# ArdulonShiled_for_Arduino_DUE.net
KiCad netlist of a schematic drawn in EAGLE
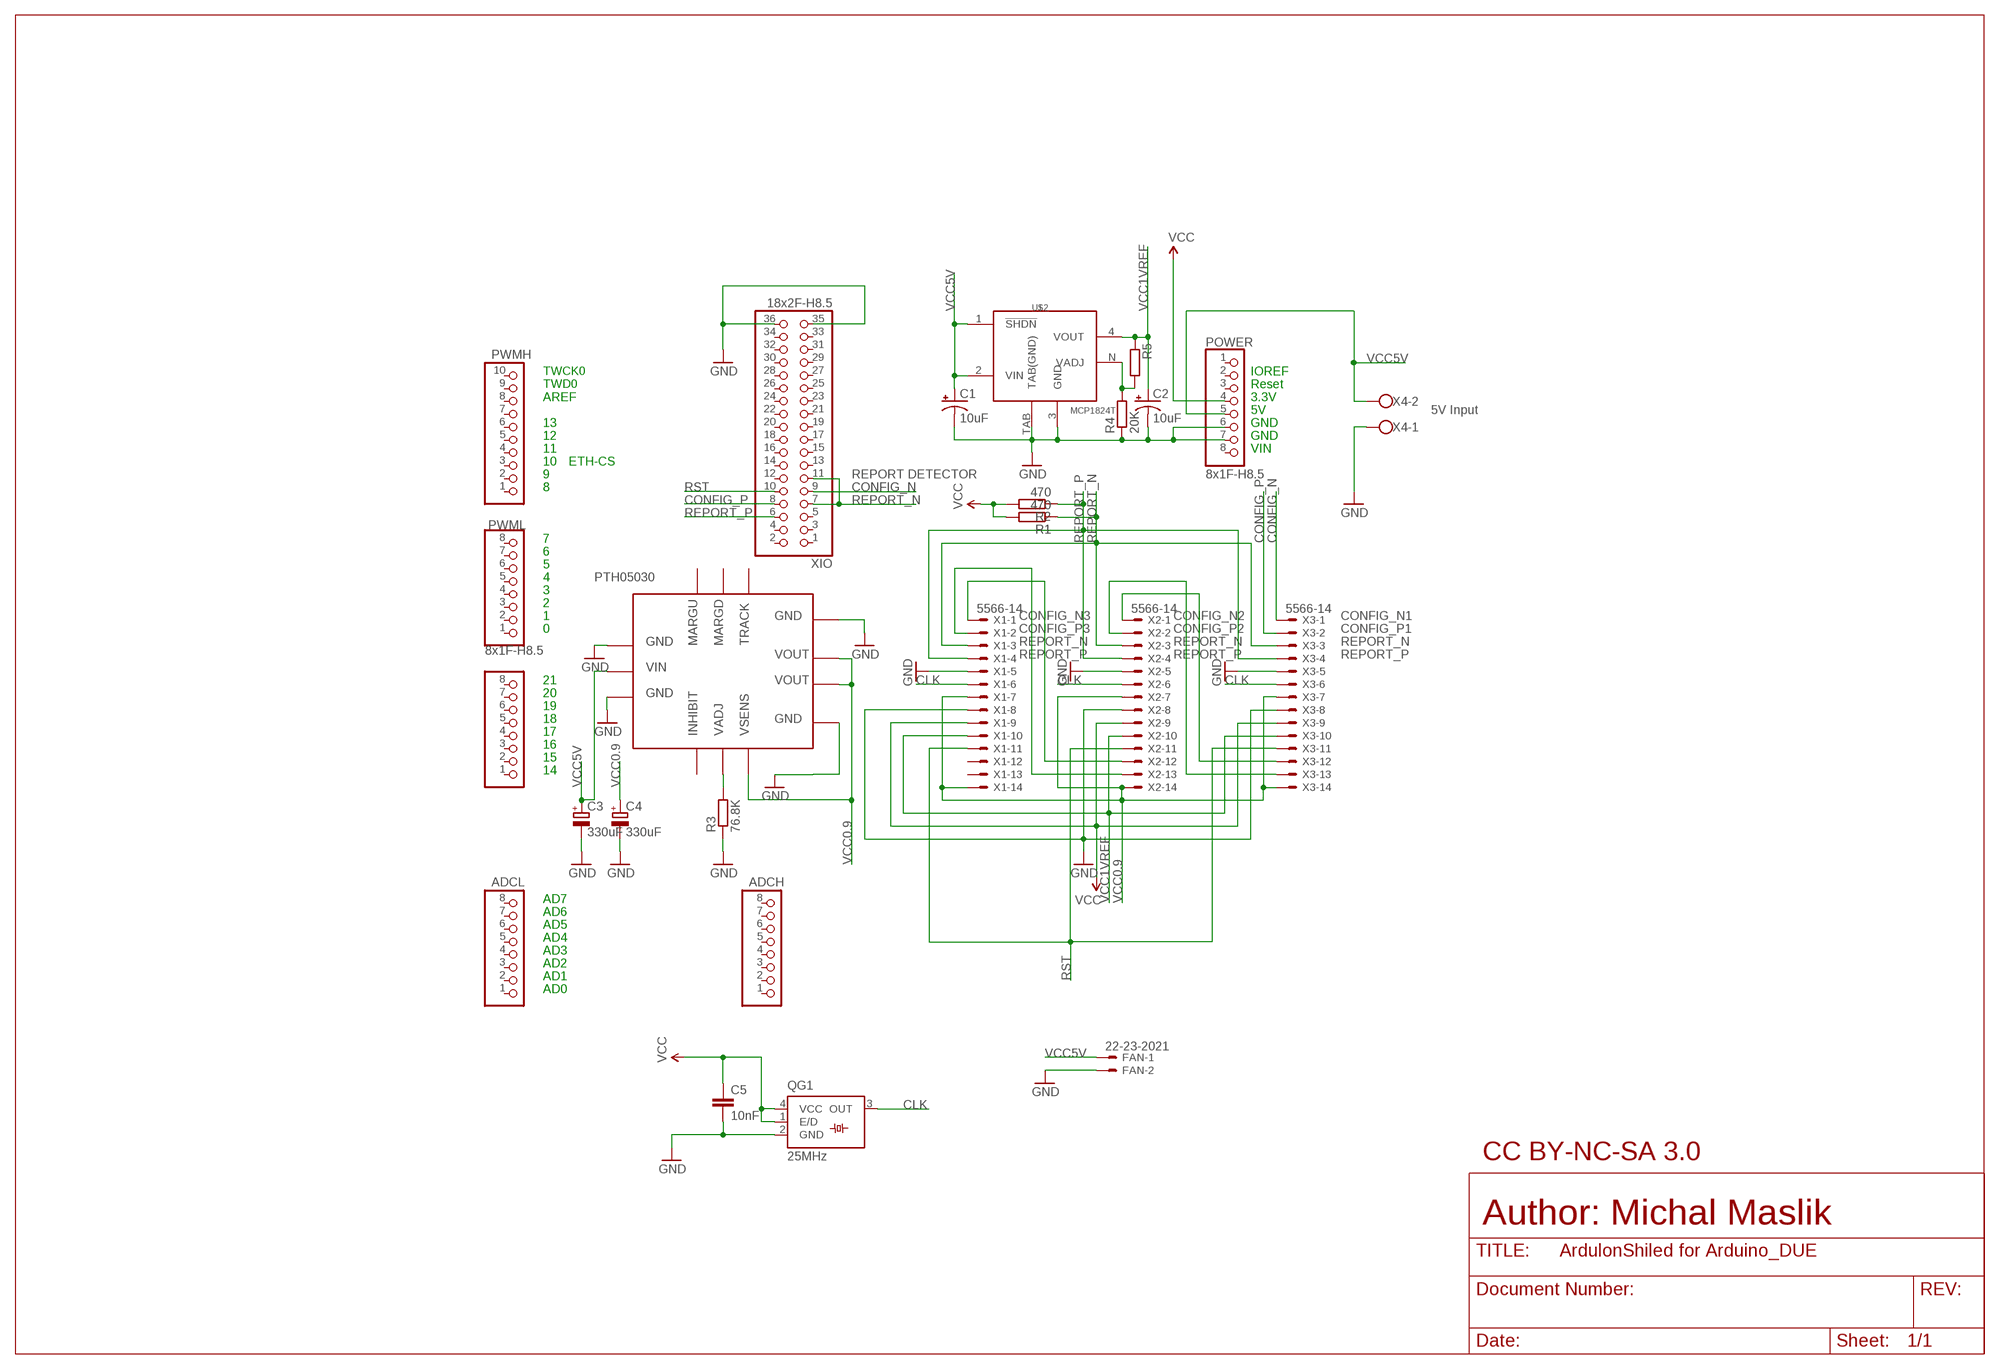
[diagram p0: schematic, sheet 1]

(export (version "E")
  (design (tool "Eeschema 10.0.6"))
  (components
    (comp (ref "ADCH")
      (value "8x1F-H8.5")
      (footprint "eagle-import:1X08")
      (libsource (lib "eagle-import") (part "PINHD-1X8"))
    )
    (comp (ref "ADCL")
      (value "8x1F-H8.5")
      (footprint "eagle-import:1X08")
      (libsource (lib "eagle-import") (part "PINHD-1X8"))
    )
    (comp (ref "C1")
      (value "10uF")
      (footprint "eagle-import:EIA3528-KIT")
      (libsource (lib "eagle-import") (part "CAP_POL3528-KIT"))
    )
    (comp (ref "C2")
      (value "10uF")
      (footprint "eagle-import:EIA3528-KIT")
      (libsource (lib "eagle-import") (part "CAP_POL3528-KIT"))
    )
    (comp (ref "C3")
      (value "330uF")
      (footprint "eagle-import:SMC_E")
      (libsource (lib "eagle-import") (part "CPOL-EUSMCE"))
    )
    (comp (ref "C4")
      (value "330uF")
      (footprint "eagle-import:SMC_E")
      (libsource (lib "eagle-import") (part "CPOL-EUSMCE"))
    )
    (comp (ref "C5")
      (value "10nF")
      (footprint "eagle-import:C0805")
      (libsource (lib "eagle-import") (part "C-EUC0805"))
    )
    (comp (ref "COMMUNICATION")
      (value "8x1F-H8.5")
      (footprint "eagle-import:1X08")
      (libsource (lib "eagle-import") (part "PINHD-1X8"))
    )
    (comp (ref "FAN")
      (value "22-23-2021")
      (footprint "eagle-import:22-23-2021")
      (libsource (lib "eagle-import") (part "22-23-2021"))
    )
    (comp (ref "POWER")
      (value "8x1F-H8.5")
      (footprint "eagle-import:1X08")
      (libsource (lib "eagle-import") (part "PINHD-1X8"))
    )
    (comp (ref "PWMH")
      (value "10x1F-H8.5")
      (footprint "eagle-import:1X10")
      (libsource (lib "eagle-import") (part "PINHD-1X10"))
    )
    (comp (ref "PWML")
      (value "8x1F-H8.5")
      (footprint "eagle-import:1X08")
      (libsource (lib "eagle-import") (part "PINHD-1X8"))
    )
    (comp (ref "QG1")
      (value "25MHz")
      (footprint "eagle-import:SM77H")
      (libsource (lib "eagle-import") (part "SM77H"))
    )
    (comp (ref "R1")
      (value "470")
      (footprint "eagle-import:M0805")
      (libsource (lib "eagle-import") (part "R-EU_M0805"))
    )
    (comp (ref "R2")
      (value "470")
      (footprint "eagle-import:M0805")
      (libsource (lib "eagle-import") (part "R-EU_M0805"))
    )
    (comp (ref "R3")
      (value "76.8K")
      (footprint "eagle-import:M0805")
      (libsource (lib "eagle-import") (part "R-EU_M0805"))
    )
    (comp (ref "R4")
      (value "20K")
      (footprint "eagle-import:M0805")
      (libsource (lib "eagle-import") (part "R-EU_M0805"))
    )
    (comp (ref "R5")
      (value "R-EU_M0805")
      (footprint "eagle-import:M0805")
      (libsource (lib "eagle-import") (part "R-EU_M0805"))
    )
    (comp (ref "U$1")
      (value "PTH05030")
      (footprint "eagle-import:PTH05030")
      (libsource (lib "eagle-import") (part "PTH05030"))
    )
    (comp (ref "U$2")
      (value "MCP1824T")
      (footprint "eagle-import:SOT223-5")
      (libsource (lib "eagle-import") (part "MCP1824T"))
    )
    (comp (ref "X1")
      (value "5566-14")
      (footprint "eagle-import:5566-14")
      (libsource (lib "eagle-import") (part "5566-14"))
    )
    (comp (ref "X2")
      (value "5566-14")
      (footprint "eagle-import:5566-14")
      (libsource (lib "eagle-import") (part "5566-14"))
    )
    (comp (ref "X3")
      (value "5566-14")
      (footprint "eagle-import:5566-14")
      (libsource (lib "eagle-import") (part "5566-14"))
    )
    (comp (ref "X4")
      (value "W237-102")
      (footprint "eagle-import:W237-102")
      (fields (field (name "MPN") "237-102"))
      (libsource (lib "eagle-import") (part "W237-102"))
    )
    (comp (ref "XIO")
      (value "18x2F-H8.5")
      (footprint "eagle-import:2X18")
      (libsource (lib "eagle-import") (part "PINHD-2X18"))
    )
  )
  (nets
    (net (code "1") (name "/CLK") (class "Default")
      (node (ref "QG1") (pin "3") (pinfunction "OUT_3") (pintype "output"))
      (node (ref "X1") (pin "6") (pinfunction "S_6") (pintype "passive"))
      (node (ref "X2") (pin "6") (pinfunction "S_6") (pintype "passive"))
      (node (ref "X3") (pin "6") (pinfunction "S_6") (pintype "passive"))
    )
    (net (code "2") (name "/CONFIG_N") (class "Default")
      (node (ref "X3") (pin "1") (pinfunction "S_1") (pintype "passive"))
      (node (ref "XIO") (pin "9") (pinfunction "9_9") (pintype "passive"))
    )
    (net (code "3") (name "/CONFIG_P") (class "Default")
      (node (ref "X3") (pin "2") (pinfunction "S_2") (pintype "passive"))
      (node (ref "XIO") (pin "8") (pinfunction "8_8") (pintype "passive"))
    )
    (net (code "4") (name "/REPORT_N") (class "Default")
      (node (ref "R1") (pin "1") (pinfunction "1_1") (pintype "passive"))
      (node (ref "X1") (pin "3") (pinfunction "S_3") (pintype "passive"))
      (node (ref "X2") (pin "3") (pinfunction "S_3") (pintype "passive"))
      (node (ref "X3") (pin "3") (pinfunction "S_3") (pintype "passive"))
      (node (ref "XIO") (pin "11") (pinfunction "11_11") (pintype "passive"))
      (node (ref "XIO") (pin "7") (pinfunction "7_7") (pintype "passive"))
    )
    (net (code "5") (name "/REPORT_P") (class "Default")
      (node (ref "R2") (pin "1") (pinfunction "1_1") (pintype "passive"))
      (node (ref "X1") (pin "4") (pinfunction "S_4") (pintype "passive"))
      (node (ref "X2") (pin "4") (pinfunction "S_4") (pintype "passive"))
      (node (ref "X3") (pin "4") (pinfunction "S_4") (pintype "passive"))
      (node (ref "XIO") (pin "6") (pinfunction "6_6") (pintype "passive"))
    )
    (net (code "6") (name "/RST") (class "Default")
      (node (ref "X1") (pin "11") (pinfunction "S_11") (pintype "passive"))
      (node (ref "X2") (pin "11") (pinfunction "S_11") (pintype "passive"))
      (node (ref "X3") (pin "11") (pinfunction "S_11") (pintype "passive"))
      (node (ref "XIO") (pin "10") (pinfunction "10_10") (pintype "passive"))
    )
    (net (code "7") (name "/VCC0.9") (class "Default")
      (node (ref "C4") (pin "+") (pinfunction "+_+") (pintype "passive"))
      (node (ref "U$1") (pin "6") (pinfunction "P$6_6") (pintype "bidirectional"))
      (node (ref "U$1") (pin "8") (pinfunction "P$8_8") (pintype "bidirectional"))
      (node (ref "U$1") (pin "9") (pinfunction "P$9_9") (pintype "bidirectional"))
      (node (ref "X1") (pin "14") (pinfunction "S_14") (pintype "passive"))
      (node (ref "X1") (pin "7") (pinfunction "S_7") (pintype "passive"))
      (node (ref "X2") (pin "14") (pinfunction "S_14") (pintype "passive"))
      (node (ref "X2") (pin "7") (pinfunction "S_7") (pintype "passive"))
      (node (ref "X3") (pin "14") (pinfunction "S_14") (pintype "passive"))
      (node (ref "X3") (pin "7") (pinfunction "S_7") (pintype "passive"))
    )
    (net (code "8") (name "/VCC1REF") (class "Default")
      (node (ref "C2") (pin "A") (pinfunction "+_A") (pintype "passive"))
      (node (ref "R5") (pin "1") (pinfunction "1_1") (pintype "passive"))
      (node (ref "U$2") (pin "4") (pinfunction "VOUT_4") (pintype "bidirectional"))
      (node (ref "X1") (pin "10") (pinfunction "S_10") (pintype "passive"))
      (node (ref "X2") (pin "10") (pinfunction "S_10") (pintype "passive"))
      (node (ref "X3") (pin "10") (pinfunction "S_10") (pintype "passive"))
    )
    (net (code "9") (name "/VCC5V") (class "Default")
      (node (ref "C1") (pin "A") (pinfunction "+_A") (pintype "passive"))
      (node (ref "C3") (pin "+") (pinfunction "+_+") (pintype "passive"))
      (node (ref "FAN") (pin "1") (pinfunction "S_1") (pintype "passive"))
      (node (ref "POWER") (pin "5") (pinfunction "5_5") (pintype "passive"))
      (node (ref "U$1") (pin "2") (pinfunction "P$2_2") (pintype "bidirectional"))
      (node (ref "U$2") (pin "1") (pinfunction "~{SHDN}_1") (pintype "bidirectional"))
      (node (ref "U$2") (pin "2") (pinfunction "VIN_2") (pintype "bidirectional"))
      (node (ref "X4") (pin "2") (pinfunction "KL_2") (pintype "passive"))
    )
    (net (code "10") (name "GND") (class "Default")
      (node (ref "C1") (pin "C") (pinfunction "-_C") (pintype "passive"))
      (node (ref "C2") (pin "C") (pinfunction "-_C") (pintype "passive"))
      (node (ref "C3") (pin "-") (pinfunction "-_-") (pintype "passive"))
      (node (ref "C4") (pin "-") (pinfunction "-_-") (pintype "passive"))
      (node (ref "C5") (pin "2") (pinfunction "2_2") (pintype "passive"))
      (node (ref "FAN") (pin "2") (pinfunction "S_2") (pintype "passive"))
      (node (ref "POWER") (pin "6") (pinfunction "6_6") (pintype "passive"))
      (node (ref "POWER") (pin "7") (pinfunction "7_7") (pintype "passive"))
      (node (ref "QG1") (pin "2") (pinfunction "GND_2") (pintype "power_in"))
      (node (ref "R3") (pin "1") (pinfunction "1_1") (pintype "passive"))
      (node (ref "R4") (pin "1") (pinfunction "1_1") (pintype "passive"))
      (node (ref "U$1") (pin "1") (pinfunction "P$1_1") (pintype "bidirectional"))
      (node (ref "U$1") (pin "10") (pinfunction "P$10_10") (pintype "bidirectional"))
      (node (ref "U$1") (pin "3") (pinfunction "P$3_3") (pintype "bidirectional"))
      (node (ref "U$1") (pin "7") (pinfunction "P$7_7") (pintype "bidirectional"))
      (node (ref "U$2") (pin "3") (pinfunction "GND_3") (pintype "bidirectional"))
      (node (ref "U$2") (pin "TAB") (pinfunction "TAB(GND)_TAB") (pintype "bidirectional"))
      (node (ref "X1") (pin "5") (pinfunction "S_5") (pintype "passive"))
      (node (ref "X1") (pin "8") (pinfunction "S_8") (pintype "passive"))
      (node (ref "X2") (pin "5") (pinfunction "S_5") (pintype "passive"))
      (node (ref "X2") (pin "8") (pinfunction "S_8") (pintype "passive"))
      (node (ref "X3") (pin "5") (pinfunction "S_5") (pintype "passive"))
      (node (ref "X3") (pin "8") (pinfunction "S_8") (pintype "passive"))
      (node (ref "X4") (pin "1") (pinfunction "KL_1") (pintype "passive"))
      (node (ref "XIO") (pin "35") (pinfunction "35_35") (pintype "passive"))
      (node (ref "XIO") (pin "36") (pinfunction "36_36") (pintype "passive"))
    )
    (net (code "11") (name "Net-(U$1-P$5)") (class "Default")
      (node (ref "R3") (pin "2") (pinfunction "2_2") (pintype "passive"))
      (node (ref "U$1") (pin "5") (pinfunction "P$5_5") (pintype "bidirectional"))
    )
    (net (code "12") (name "Net-(U$2-VADJ)") (class "Default")
      (node (ref "R4") (pin "2") (pinfunction "2_2") (pintype "passive"))
      (node (ref "R5") (pin "2") (pinfunction "2_2") (pintype "passive"))
      (node (ref "U$2") (pin "N") (pinfunction "VADJ_N") (pintype "bidirectional"))
    )
    (net (code "13") (name "Net-(X1A-S)") (class "Default")
      (node (ref "X1") (pin "1") (pinfunction "S_1") (pintype "passive"))
      (node (ref "X2") (pin "12") (pinfunction "S_12") (pintype "passive"))
    )
    (net (code "14") (name "Net-(X1G-S)") (class "Default")
      (node (ref "X1") (pin "2") (pinfunction "S_2") (pintype "passive"))
      (node (ref "X2") (pin "13") (pinfunction "S_13") (pintype "passive"))
    )
    (net (code "15") (name "Net-(X2A-S)") (class "Default")
      (node (ref "X2") (pin "1") (pinfunction "S_1") (pintype "passive"))
      (node (ref "X3") (pin "12") (pinfunction "S_12") (pintype "passive"))
    )
    (net (code "16") (name "Net-(X2G-S)") (class "Default")
      (node (ref "X2") (pin "2") (pinfunction "S_2") (pintype "passive"))
      (node (ref "X3") (pin "13") (pinfunction "S_13") (pintype "passive"))
    )
    (net (code "17") (name "VCC") (class "Default")
      (node (ref "C5") (pin "1") (pinfunction "1_1") (pintype "passive"))
      (node (ref "POWER") (pin "4") (pinfunction "4_4") (pintype "passive"))
      (node (ref "QG1") (pin "1") (pinfunction "E/D_1") (pintype "input"))
      (node (ref "QG1") (pin "4") (pinfunction "VCC_4") (pintype "power_in"))
      (node (ref "R1") (pin "2") (pinfunction "2_2") (pintype "passive"))
      (node (ref "R2") (pin "2") (pinfunction "2_2") (pintype "passive"))
      (node (ref "X1") (pin "9") (pinfunction "S_9") (pintype "passive"))
      (node (ref "X2") (pin "9") (pinfunction "S_9") (pintype "passive"))
      (node (ref "X3") (pin "9") (pinfunction "S_9") (pintype "passive"))
    )
    (net (code "18") (name "unconnected-(ADCH-Pad1)") (class "Default")
      (node (ref "ADCH") (pin "1") (pinfunction "1_1") (pintype "passive"))
    )
    (net (code "19") (name "unconnected-(ADCH-Pad2)") (class "Default")
      (node (ref "ADCH") (pin "2") (pinfunction "2_2") (pintype "passive"))
    )
    (net (code "20") (name "unconnected-(ADCH-Pad3)") (class "Default")
      (node (ref "ADCH") (pin "3") (pinfunction "3_3") (pintype "passive"))
    )
    (net (code "21") (name "unconnected-(ADCH-Pad4)") (class "Default")
      (node (ref "ADCH") (pin "4") (pinfunction "4_4") (pintype "passive"))
    )
    (net (code "22") (name "unconnected-(ADCH-Pad5)") (class "Default")
      (node (ref "ADCH") (pin "5") (pinfunction "5_5") (pintype "passive"))
    )
    (net (code "23") (name "unconnected-(ADCH-Pad6)") (class "Default")
      (node (ref "ADCH") (pin "6") (pinfunction "6_6") (pintype "passive"))
    )
    (net (code "24") (name "unconnected-(ADCH-Pad7)") (class "Default")
      (node (ref "ADCH") (pin "7") (pinfunction "7_7") (pintype "passive"))
    )
    (net (code "25") (name "unconnected-(ADCH-Pad8)") (class "Default")
      (node (ref "ADCH") (pin "8") (pinfunction "8_8") (pintype "passive"))
    )
    (net (code "26") (name "unconnected-(ADCL-Pad1)") (class "Default")
      (node (ref "ADCL") (pin "1") (pinfunction "1_1") (pintype "passive"))
    )
    (net (code "27") (name "unconnected-(ADCL-Pad2)") (class "Default")
      (node (ref "ADCL") (pin "2") (pinfunction "2_2") (pintype "passive"))
    )
    (net (code "28") (name "unconnected-(ADCL-Pad3)") (class "Default")
      (node (ref "ADCL") (pin "3") (pinfunction "3_3") (pintype "passive"))
    )
    (net (code "29") (name "unconnected-(ADCL-Pad4)") (class "Default")
      (node (ref "ADCL") (pin "4") (pinfunction "4_4") (pintype "passive"))
    )
    (net (code "30") (name "unconnected-(ADCL-Pad5)") (class "Default")
      (node (ref "ADCL") (pin "5") (pinfunction "5_5") (pintype "passive"))
    )
    (net (code "31") (name "unconnected-(ADCL-Pad6)") (class "Default")
      (node (ref "ADCL") (pin "6") (pinfunction "6_6") (pintype "passive"))
    )
    (net (code "32") (name "unconnected-(ADCL-Pad7)") (class "Default")
      (node (ref "ADCL") (pin "7") (pinfunction "7_7") (pintype "passive"))
    )
    (net (code "33") (name "unconnected-(ADCL-Pad8)") (class "Default")
      (node (ref "ADCL") (pin "8") (pinfunction "8_8") (pintype "passive"))
    )
    (net (code "34") (name "unconnected-(COMMUNICATION-Pad1)") (class "Default")
      (node (ref "COMMUNICATION") (pin "1") (pinfunction "1_1") (pintype "passive"))
    )
    (net (code "35") (name "unconnected-(COMMUNICATION-Pad2)") (class "Default")
      (node (ref "COMMUNICATION") (pin "2") (pinfunction "2_2") (pintype "passive"))
    )
    (net (code "36") (name "unconnected-(COMMUNICATION-Pad3)") (class "Default")
      (node (ref "COMMUNICATION") (pin "3") (pinfunction "3_3") (pintype "passive"))
    )
    (net (code "37") (name "unconnected-(COMMUNICATION-Pad4)") (class "Default")
      (node (ref "COMMUNICATION") (pin "4") (pinfunction "4_4") (pintype "passive"))
    )
    (net (code "38") (name "unconnected-(COMMUNICATION-Pad5)") (class "Default")
      (node (ref "COMMUNICATION") (pin "5") (pinfunction "5_5") (pintype "passive"))
    )
    (net (code "39") (name "unconnected-(COMMUNICATION-Pad6)") (class "Default")
      (node (ref "COMMUNICATION") (pin "6") (pinfunction "6_6") (pintype "passive"))
    )
    (net (code "40") (name "unconnected-(COMMUNICATION-Pad7)") (class "Default")
      (node (ref "COMMUNICATION") (pin "7") (pinfunction "7_7") (pintype "passive"))
    )
    (net (code "41") (name "unconnected-(COMMUNICATION-Pad8)") (class "Default")
      (node (ref "COMMUNICATION") (pin "8") (pinfunction "8_8") (pintype "passive"))
    )
    (net (code "42") (name "unconnected-(POWER-Pad1)") (class "Default")
      (node (ref "POWER") (pin "1") (pinfunction "1_1") (pintype "passive"))
    )
    (net (code "43") (name "unconnected-(POWER-Pad2)") (class "Default")
      (node (ref "POWER") (pin "2") (pinfunction "2_2") (pintype "passive"))
    )
    (net (code "44") (name "unconnected-(POWER-Pad3)") (class "Default")
      (node (ref "POWER") (pin "3") (pinfunction "3_3") (pintype "passive"))
    )
    (net (code "45") (name "unconnected-(POWER-Pad8)") (class "Default")
      (node (ref "POWER") (pin "8") (pinfunction "8_8") (pintype "passive"))
    )
    (net (code "46") (name "unconnected-(PWMH-Pad1)") (class "Default")
      (node (ref "PWMH") (pin "1") (pinfunction "1_1") (pintype "passive"))
    )
    (net (code "47") (name "unconnected-(PWMH-Pad2)") (class "Default")
      (node (ref "PWMH") (pin "2") (pinfunction "2_2") (pintype "passive"))
    )
    (net (code "48") (name "unconnected-(PWMH-Pad3)") (class "Default")
      (node (ref "PWMH") (pin "3") (pinfunction "3_3") (pintype "passive"))
    )
    (net (code "49") (name "unconnected-(PWMH-Pad4)") (class "Default")
      (node (ref "PWMH") (pin "4") (pinfunction "4_4") (pintype "passive"))
    )
    (net (code "50") (name "unconnected-(PWMH-Pad5)") (class "Default")
      (node (ref "PWMH") (pin "5") (pinfunction "5_5") (pintype "passive"))
    )
    (net (code "51") (name "unconnected-(PWMH-Pad6)") (class "Default")
      (node (ref "PWMH") (pin "6") (pinfunction "6_6") (pintype "passive"))
    )
    (net (code "52") (name "unconnected-(PWMH-Pad7)") (class "Default")
      (node (ref "PWMH") (pin "7") (pinfunction "7_7") (pintype "passive"))
    )
    (net (code "53") (name "unconnected-(PWMH-Pad8)") (class "Default")
      (node (ref "PWMH") (pin "8") (pinfunction "8_8") (pintype "passive"))
    )
    (net (code "54") (name "unconnected-(PWMH-Pad9)") (class "Default")
      (node (ref "PWMH") (pin "9") (pinfunction "9_9") (pintype "passive"))
    )
    (net (code "55") (name "unconnected-(PWMH-Pad10)") (class "Default")
      (node (ref "PWMH") (pin "10") (pinfunction "10_10") (pintype "passive"))
    )
    (net (code "56") (name "unconnected-(PWML-Pad1)") (class "Default")
      (node (ref "PWML") (pin "1") (pinfunction "1_1") (pintype "passive"))
    )
    (net (code "57") (name "unconnected-(PWML-Pad2)") (class "Default")
      (node (ref "PWML") (pin "2") (pinfunction "2_2") (pintype "passive"))
    )
    (net (code "58") (name "unconnected-(PWML-Pad3)") (class "Default")
      (node (ref "PWML") (pin "3") (pinfunction "3_3") (pintype "passive"))
    )
    (net (code "59") (name "unconnected-(PWML-Pad4)") (class "Default")
      (node (ref "PWML") (pin "4") (pinfunction "4_4") (pintype "passive"))
    )
    (net (code "60") (name "unconnected-(PWML-Pad5)") (class "Default")
      (node (ref "PWML") (pin "5") (pinfunction "5_5") (pintype "passive"))
    )
    (net (code "61") (name "unconnected-(PWML-Pad6)") (class "Default")
      (node (ref "PWML") (pin "6") (pinfunction "6_6") (pintype "passive"))
    )
    (net (code "62") (name "unconnected-(PWML-Pad7)") (class "Default")
      (node (ref "PWML") (pin "7") (pinfunction "7_7") (pintype "passive"))
    )
    (net (code "63") (name "unconnected-(PWML-Pad8)") (class "Default")
      (node (ref "PWML") (pin "8") (pinfunction "8_8") (pintype "passive"))
    )
    (net (code "64") (name "unconnected-(U$1-P$4-Pad4)") (class "Default")
      (node (ref "U$1") (pin "4") (pinfunction "P$4_4") (pintype "bidirectional"))
    )
    (net (code "65") (name "unconnected-(U$1-P$11-Pad11)") (class "Default")
      (node (ref "U$1") (pin "11") (pinfunction "P$11_11") (pintype "bidirectional"))
    )
    (net (code "66") (name "unconnected-(U$1-P$12-Pad12)") (class "Default")
      (node (ref "U$1") (pin "12") (pinfunction "P$12_12") (pintype "bidirectional"))
    )
    (net (code "67") (name "unconnected-(U$1-P$13-Pad13)") (class "Default")
      (node (ref "U$1") (pin "13") (pinfunction "P$13_13") (pintype "bidirectional"))
    )
    (net (code "68") (name "unconnected-(X1D-S-Pad12)") (class "Default")
      (node (ref "X1") (pin "12") (pinfunction "S_12") (pintype "passive"))
    )
    (net (code "69") (name "unconnected-(X1E-S-Pad13)") (class "Default")
      (node (ref "X1") (pin "13") (pinfunction "S_13") (pintype "passive"))
    )
    (net (code "70") (name "unconnected-(XIO-Pad1)") (class "Default")
      (node (ref "XIO") (pin "1") (pinfunction "1_1") (pintype "passive"))
    )
    (net (code "71") (name "unconnected-(XIO-Pad2)") (class "Default")
      (node (ref "XIO") (pin "2") (pinfunction "2_2") (pintype "passive"))
    )
    (net (code "72") (name "unconnected-(XIO-Pad3)") (class "Default")
      (node (ref "XIO") (pin "3") (pinfunction "3_3") (pintype "passive"))
    )
    (net (code "73") (name "unconnected-(XIO-Pad4)") (class "Default")
      (node (ref "XIO") (pin "4") (pinfunction "4_4") (pintype "passive"))
    )
    (net (code "74") (name "unconnected-(XIO-Pad5)") (class "Default")
      (node (ref "XIO") (pin "5") (pinfunction "5_5") (pintype "passive"))
    )
    (net (code "75") (name "unconnected-(XIO-Pad12)") (class "Default")
      (node (ref "XIO") (pin "12") (pinfunction "12_12") (pintype "passive"))
    )
    (net (code "76") (name "unconnected-(XIO-Pad13)") (class "Default")
      (node (ref "XIO") (pin "13") (pinfunction "13_13") (pintype "passive"))
    )
    (net (code "77") (name "unconnected-(XIO-Pad14)") (class "Default")
      (node (ref "XIO") (pin "14") (pinfunction "14_14") (pintype "passive"))
    )
    (net (code "78") (name "unconnected-(XIO-Pad15)") (class "Default")
      (node (ref "XIO") (pin "15") (pinfunction "15_15") (pintype "passive"))
    )
    (net (code "79") (name "unconnected-(XIO-Pad16)") (class "Default")
      (node (ref "XIO") (pin "16") (pinfunction "16_16") (pintype "passive"))
    )
    (net (code "80") (name "unconnected-(XIO-Pad17)") (class "Default")
      (node (ref "XIO") (pin "17") (pinfunction "17_17") (pintype "passive"))
    )
    (net (code "81") (name "unconnected-(XIO-Pad18)") (class "Default")
      (node (ref "XIO") (pin "18") (pinfunction "18_18") (pintype "passive"))
    )
    (net (code "82") (name "unconnected-(XIO-Pad19)") (class "Default")
      (node (ref "XIO") (pin "19") (pinfunction "19_19") (pintype "passive"))
    )
    (net (code "83") (name "unconnected-(XIO-Pad20)") (class "Default")
      (node (ref "XIO") (pin "20") (pinfunction "20_20") (pintype "passive"))
    )
    (net (code "84") (name "unconnected-(XIO-Pad21)") (class "Default")
      (node (ref "XIO") (pin "21") (pinfunction "21_21") (pintype "passive"))
    )
    (net (code "85") (name "unconnected-(XIO-Pad22)") (class "Default")
      (node (ref "XIO") (pin "22") (pinfunction "22_22") (pintype "passive"))
    )
    (net (code "86") (name "unconnected-(XIO-Pad23)") (class "Default")
      (node (ref "XIO") (pin "23") (pinfunction "23_23") (pintype "passive"))
    )
    (net (code "87") (name "unconnected-(XIO-Pad24)") (class "Default")
      (node (ref "XIO") (pin "24") (pinfunction "24_24") (pintype "passive"))
    )
    (net (code "88") (name "unconnected-(XIO-Pad25)") (class "Default")
      (node (ref "XIO") (pin "25") (pinfunction "25_25") (pintype "passive"))
    )
    (net (code "89") (name "unconnected-(XIO-Pad26)") (class "Default")
      (node (ref "XIO") (pin "26") (pinfunction "26_26") (pintype "passive"))
    )
    (net (code "90") (name "unconnected-(XIO-Pad27)") (class "Default")
      (node (ref "XIO") (pin "27") (pinfunction "27_27") (pintype "passive"))
    )
    (net (code "91") (name "unconnected-(XIO-Pad28)") (class "Default")
      (node (ref "XIO") (pin "28") (pinfunction "28_28") (pintype "passive"))
    )
    (net (code "92") (name "unconnected-(XIO-Pad29)") (class "Default")
      (node (ref "XIO") (pin "29") (pinfunction "29_29") (pintype "passive"))
    )
    (net (code "93") (name "unconnected-(XIO-Pad30)") (class "Default")
      (node (ref "XIO") (pin "30") (pinfunction "30_30") (pintype "passive"))
    )
    (net (code "94") (name "unconnected-(XIO-Pad31)") (class "Default")
      (node (ref "XIO") (pin "31") (pinfunction "31_31") (pintype "passive"))
    )
    (net (code "95") (name "unconnected-(XIO-Pad32)") (class "Default")
      (node (ref "XIO") (pin "32") (pinfunction "32_32") (pintype "passive"))
    )
    (net (code "96") (name "unconnected-(XIO-Pad33)") (class "Default")
      (node (ref "XIO") (pin "33") (pinfunction "33_33") (pintype "passive"))
    )
    (net (code "97") (name "unconnected-(XIO-Pad34)") (class "Default")
      (node (ref "XIO") (pin "34") (pinfunction "34_34") (pintype "passive"))
    )
  )
)
